# 1A_power_supply.net
KiCad netlist of a schematic drawn in EAGLE
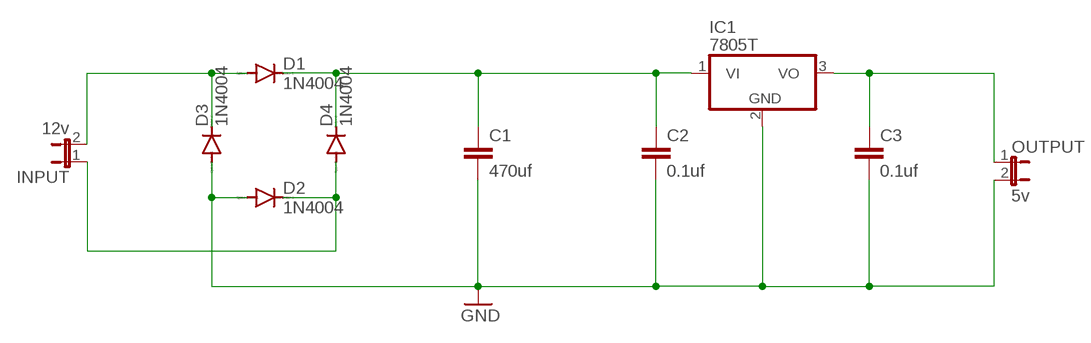
[diagram p0: schematic, sheet 1]

(export (version "E")
  (design (tool "Eeschema 10.0.6"))
  (components
    (comp (ref "C1")
      (value "470uf")
      (footprint "eagle-import:C2.5-2")
      (libsource (lib "eagle-import") (part "C2.5/2"))
    )
    (comp (ref "C2")
      (value "0.1uf")
      (footprint "eagle-import:C2.5-2")
      (libsource (lib "eagle-import") (part "C2.5/2"))
    )
    (comp (ref "C3")
      (value "0.1uf")
      (footprint "eagle-import:C2.5-2")
      (libsource (lib "eagle-import") (part "C2.5/2"))
    )
    (comp (ref "D1")
      (value "1N4004")
      (footprint "eagle-import:DO41-10")
      (libsource (lib "eagle-import") (part "1N4004"))
    )
    (comp (ref "D2")
      (value "1N4004")
      (footprint "eagle-import:DO41-10")
      (libsource (lib "eagle-import") (part "1N4004"))
    )
    (comp (ref "D3")
      (value "1N4004")
      (footprint "eagle-import:DO41-10")
      (libsource (lib "eagle-import") (part "1N4004"))
    )
    (comp (ref "D4")
      (value "1N4004")
      (footprint "eagle-import:DO41-10")
      (libsource (lib "eagle-import") (part "1N4004"))
    )
    (comp (ref "IC1")
      (value "7805T")
      (footprint "eagle-import:TO220H")
      (libsource (lib "eagle-import") (part "78T05"))
    )
    (comp (ref "INPUT")
      (value "12v")
      (footprint "eagle-import:JP1")
      (libsource (lib "eagle-import") (part "JP1E"))
    )
    (comp (ref "OUTPUT")
      (value "5v")
      (footprint "eagle-import:JP1")
      (libsource (lib "eagle-import") (part "JP1E"))
    )
  )
  (nets
    (net (code "1") (name "GND") (class "Default")
      (node (ref "C1") (pin "2") (pinfunction "2_2") (pintype "passive"))
      (node (ref "C2") (pin "2") (pinfunction "2_2") (pintype "passive"))
      (node (ref "C3") (pin "2") (pinfunction "2_2") (pintype "passive"))
      (node (ref "D2") (pin "A") (pinfunction "A_A") (pintype "passive"))
      (node (ref "D3") (pin "A") (pinfunction "A_A") (pintype "passive"))
      (node (ref "IC1") (pin "2") (pinfunction "GND_2") (pintype "passive"))
      (node (ref "OUTPUT") (pin "2") (pinfunction "2_2") (pintype "passive"))
    )
    (net (code "2") (name "Net-(D1-PadA)") (class "Default")
      (node (ref "D1") (pin "A") (pinfunction "A_A") (pintype "passive"))
      (node (ref "D3") (pin "C") (pinfunction "C_C") (pintype "passive"))
      (node (ref "INPUT") (pin "2") (pinfunction "2_2") (pintype "passive"))
    )
    (net (code "3") (name "Net-(D2-PadC)") (class "Default")
      (node (ref "D2") (pin "C") (pinfunction "C_C") (pintype "passive"))
      (node (ref "D4") (pin "A") (pinfunction "A_A") (pintype "passive"))
      (node (ref "INPUT") (pin "1") (pinfunction "1_1") (pintype "passive"))
    )
    (net (code "4") (name "Net-(IC1-VI)") (class "Default")
      (node (ref "C1") (pin "1") (pinfunction "1_1") (pintype "passive"))
      (node (ref "C2") (pin "1") (pinfunction "1_1") (pintype "passive"))
      (node (ref "D1") (pin "C") (pinfunction "C_C") (pintype "passive"))
      (node (ref "D4") (pin "C") (pinfunction "C_C") (pintype "passive"))
      (node (ref "IC1") (pin "1") (pinfunction "VI_1") (pintype "input"))
    )
    (net (code "5") (name "Net-(IC1-VO)") (class "Default")
      (node (ref "C3") (pin "1") (pinfunction "1_1") (pintype "passive"))
      (node (ref "IC1") (pin "3") (pinfunction "VO_3") (pintype "passive"))
      (node (ref "OUTPUT") (pin "1") (pinfunction "1_1") (pintype "passive"))
    )
  )
)
